# PCB_mezzanine_clock_template.net
KiCad netlist of a schematic drawn in Altium Designer
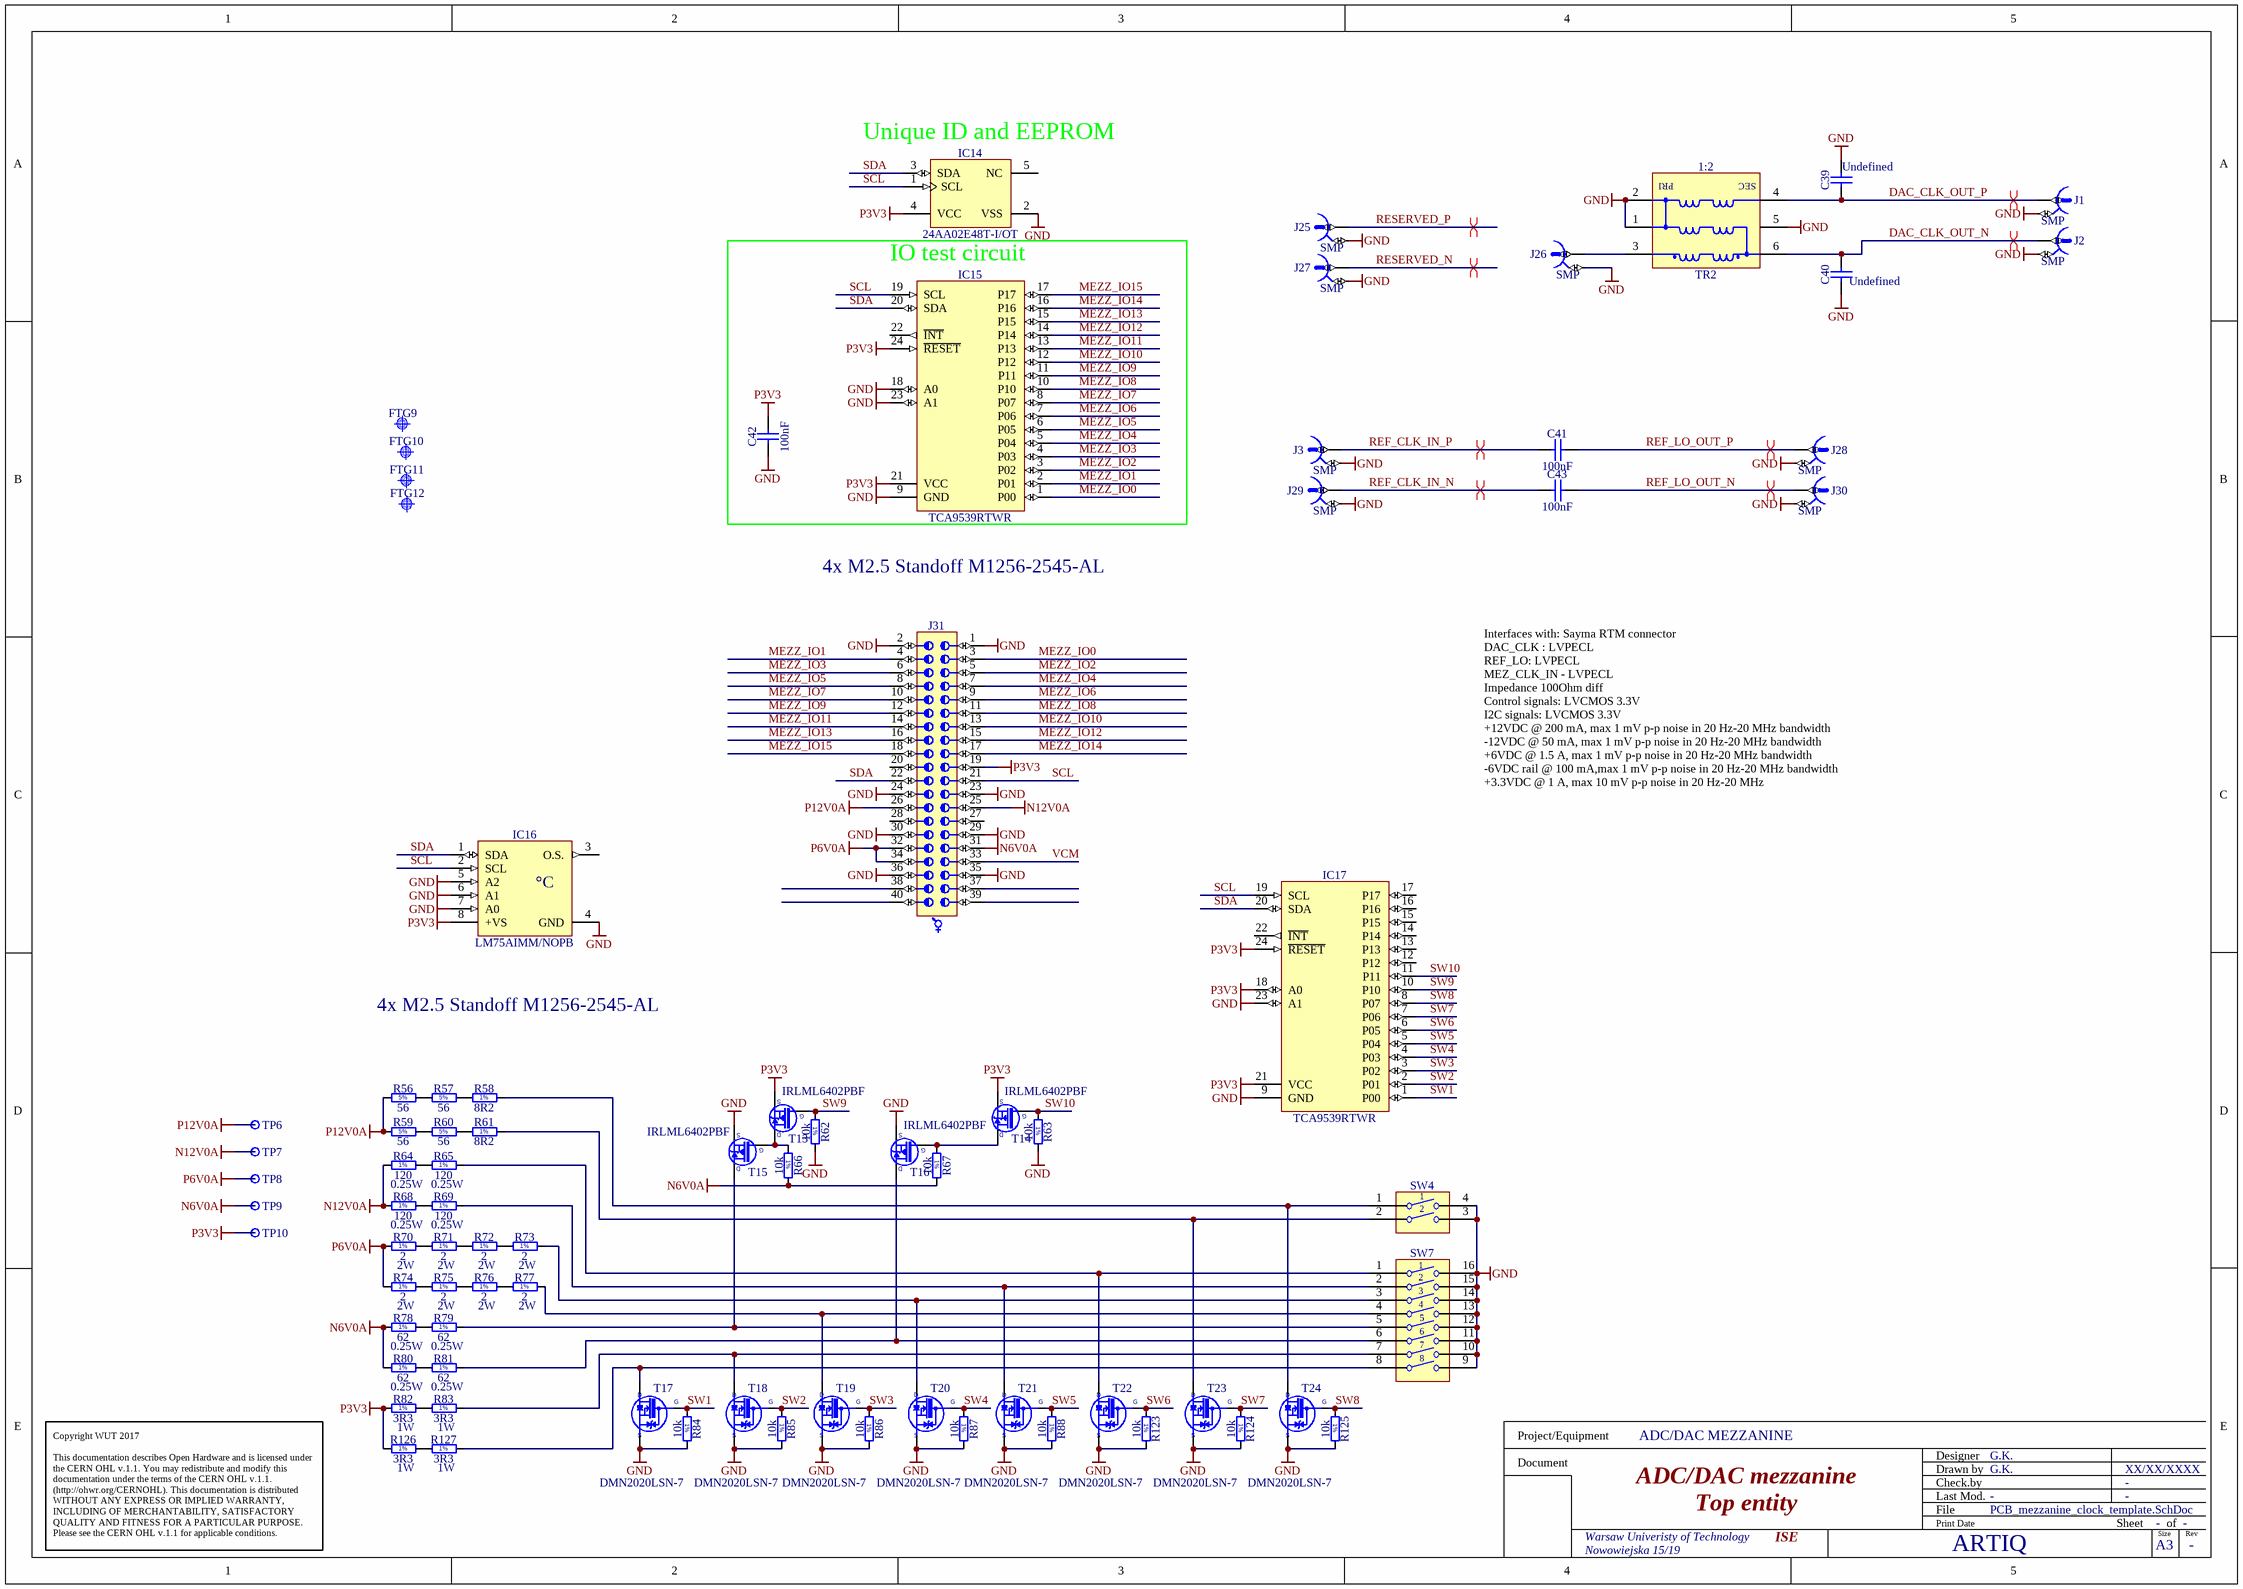
[diagram p0: PCB_mezzanine_clock_template.SchDoc]

(export (version "E")
  (design (tool "Eeschema 10.0.6"))
  (components
    (comp (ref "C39")
      (value "Undefined")
      (footprint "CAPC1005X55N")
      (description "Non-polarised capacitor")
      (fields (field (name "PART NUMBER") "CC0402_NO-VALUE") (field (name "AUTHOR") "CERN DEM JLC"))
      (libsource (lib "Capacitors") (part "Capacitor - non polarized"))
    )
    (comp (ref "C40")
      (value "Undefined")
      (footprint "CAPC1005X55N")
      (description "Non-polarised capacitor")
      (fields (field (name "PART NUMBER") "CC0402_NO-VALUE") (field (name "AUTHOR") "CERN DEM JLC"))
      (libsource (lib "Capacitors") (part "Capacitor - non polarized"))
    )
    (comp (ref "C41")
      (value "100nF")
      (footprint "CAPC1005X55N")
      (description "Non-polarised capacitor")
      (fields
        (field (name "PART NUMBER") "CC0402_100NF_16V_10%_X5R")
        (field (name "VOLTAGE") "16V")
        (field (name "AUTHOR") "CERN DEM JLC")
      )
      (libsource (lib "Capacitors") (part "Capacitor - non polarized"))
    )
    (comp (ref "C42")
      (value "100nF")
      (footprint "CAPC1005X55N")
      (description "Non-polarised capacitor")
      (fields
        (field (name "PART NUMBER") "CC0402_100NF_16V_10%_X5R")
        (field (name "VOLTAGE") "16V")
        (field (name "AUTHOR") "CERN DEM JLC")
      )
      (libsource (lib "Capacitors") (part "Capacitor - non polarized"))
    )
    (comp (ref "C43")
      (value "100nF")
      (footprint "CAPC1005X55N")
      (description "Non-polarised capacitor")
      (fields
        (field (name "PART NUMBER") "CC0402_100NF_16V_10%_X5R")
        (field (name "VOLTAGE") "16V")
        (field (name "AUTHOR") "CERN DEM JLC")
      )
      (libsource (lib "Capacitors") (part "Capacitor - non polarized"))
    )
    (comp (ref "FTG9")
      (value "Use only in PCB")
      (footprint "FIDUCIAL_TOP_C100-200")
      (description "Fiducial Target")
      (fields (field (name "PART NUMBER") "FIDUCIAL_TARGET_C100-200") (field (name "AUTHOR") "CERN DEM JLC"))
      (libsource (lib "Eletro-mechanical") (part "Fiducial Target"))
    )
    (comp (ref "FTG10")
      (value "Use only in PCB")
      (footprint "FIDUCIAL_TOP_S100-200")
      (description "Fiducial Target")
      (fields (field (name "PART NUMBER") "FIDUCIAL_TARGET_S100-200") (field (name "AUTHOR") "CERN DEM JLC"))
      (libsource (lib "Eletro-mechanical") (part "Fiducial Target"))
    )
    (comp (ref "FTG11")
      (value "Use only in PCB")
      (footprint "FIDUCIAL_TOP_S200-400")
      (description "Fiducial Target")
      (fields (field (name "PART NUMBER") "FIDUCIAL_TARGET_S200-400") (field (name "AUTHOR") "CERN DEM JLC"))
      (libsource (lib "Eletro-mechanical") (part "Fiducial Target"))
    )
    (comp (ref "FTG12")
      (value "Use only in PCB")
      (footprint "FIDUCIAL_TOP_S100-200")
      (description "Fiducial Target")
      (fields (field (name "PART NUMBER") "FIDUCIAL_TARGET_S100-200") (field (name "AUTHOR") "CERN DEM JLC"))
      (libsource (lib "Eletro-mechanical") (part "Fiducial Target"))
    )
    (comp (ref "IC14")
      (value "24AA02E48T-I/OT")
      (footprint "SOT95P280X145-5N")
      (description "1.7V-5.5V, 2K I2C Serial EEPROM With EUI-48 Node Identity")
      (fields (field (name "MANUFACTURER") "MICROCHIP TECHNOLOGY") (field (name "AUTHOR") "CERN DEM MR"))
      (libsource (lib "ICs And Semiconductors") (part "24AA02E48T-I/OT"))
    )
    (comp (ref "IC15")
      (value "TCA9539RTWR")
      (footprint "QFN50P400X400X80-25N-S255")
      (description "Low-Voltage 16-Bit I2C and SMBus I/O Expander")
      (fields (field (name "MANUFACTURER") "TEXAS INSTRUMENTS") (field (name "AUTHOR") "CERN DEM MR"))
      (libsource (lib "ICs And Semiconductors") (part "TCA9539RTWR"))
    )
    (comp (ref "IC16")
      (value "LM75AIMM/NOPB")
      (footprint "SOP65P490X109-8N")
      (description "Digital Temperature Sensor and Thermal Watchdog with Two-Wire Interface")
      (fields (field (name "MANUFACTURER") "TEXAS INSTRUMENTS") (field (name "AUTHOR") "CERN DEM JLC"))
      (libsource (lib "ICs And Semiconductors") (part "LM75"))
    )
    (comp (ref "IC17")
      (value "TCA9539RTWR")
      (footprint "QFN50P400X400X80-25N-S255")
      (description "Low-Voltage 16-Bit I2C and SMBus I/O Expander")
      (fields (field (name "MANUFACTURER") "TEXAS INSTRUMENTS") (field (name "AUTHOR") "CERN DEM MR"))
      (libsource (lib "ICs And Semiconductors") (part "TCA9539RTWR"))
    )
    (comp (ref "J1")
      (value "SMP")
      (footprint "MOLEX_85305-0232")
      (fields
        (field (name "PART NUMBER") "MOLEX_85305-0232")
        (field (name "MANUFACTURER") "MOLEX")
        (field (name "MANUFACTURER PART NUMBER") "85305-0232")
        (field (name "AUTHOR") "CERN DEM JMW")
      )
      (libsource (lib "") (part "Coax_1Male_1Shield_1"))
    )
    (comp (ref "J2")
      (value "SMP")
      (footprint "MOLEX_85305-0232")
      (fields
        (field (name "PART NUMBER") "MOLEX_85305-0232")
        (field (name "MANUFACTURER") "MOLEX")
        (field (name "MANUFACTURER PART NUMBER") "85305-0232")
        (field (name "AUTHOR") "CERN DEM JMW")
      )
      (libsource (lib "") (part "Coax_1Male_1Shield_1"))
    )
    (comp (ref "J3")
      (value "SMP")
      (footprint "MOLEX_85305-0232")
      (fields
        (field (name "PART NUMBER") "MOLEX_85305-0232")
        (field (name "MANUFACTURER") "MOLEX")
        (field (name "MANUFACTURER PART NUMBER") "85305-0232")
        (field (name "AUTHOR") "CERN DEM JMW")
      )
      (libsource (lib "Connectors") (part "Coax_1Male_1Shield"))
    )
    (comp (ref "J25")
      (value "SMP")
      (footprint "MOLEX_85305-0232")
      (fields
        (field (name "PART NUMBER") "MOLEX_85305-0232")
        (field (name "MANUFACTURER") "MOLEX")
        (field (name "MANUFACTURER PART NUMBER") "85305-0232")
        (field (name "AUTHOR") "CERN DEM JMW")
      )
      (libsource (lib "Connectors") (part "Coax_1Male_1Shield"))
    )
    (comp (ref "J26")
      (value "SMP")
      (footprint "MOLEX_73415-3591")
      (fields
        (field (name "PART NUMBER") "MOLEX_73415-3591")
        (field (name "MANUFACTURER") "MOLEX")
        (field (name "MANUFACTURER PART NUMBER") "73415-3591")
        (field (name "AUTHOR") "CERN DEM JMW")
      )
      (libsource (lib "Connectors") (part "Coax_1Male_1Shield"))
    )
    (comp (ref "J27")
      (value "SMP")
      (footprint "MOLEX_85305-0232")
      (fields
        (field (name "PART NUMBER") "MOLEX_85305-0232")
        (field (name "MANUFACTURER") "MOLEX")
        (field (name "MANUFACTURER PART NUMBER") "85305-0232")
        (field (name "AUTHOR") "CERN DEM JMW")
      )
      (libsource (lib "Connectors") (part "Coax_1Male_1Shield"))
    )
    (comp (ref "J28")
      (value "SMP")
      (footprint "MOLEX_85305-0232")
      (fields
        (field (name "PART NUMBER") "MOLEX_85305-0232")
        (field (name "MANUFACTURER") "MOLEX")
        (field (name "MANUFACTURER PART NUMBER") "85305-0232")
        (field (name "AUTHOR") "CERN DEM JMW")
      )
      (libsource (lib "") (part "Coax_1Male_1Shield_1"))
    )
    (comp (ref "J29")
      (value "SMP")
      (footprint "MOLEX_85305-0232")
      (fields
        (field (name "PART NUMBER") "MOLEX_85305-0232")
        (field (name "MANUFACTURER") "MOLEX")
        (field (name "MANUFACTURER PART NUMBER") "85305-0232")
        (field (name "AUTHOR") "CERN DEM JMW")
      )
      (libsource (lib "Connectors") (part "Coax_1Male_1Shield"))
    )
    (comp (ref "J30")
      (value "SMP")
      (footprint "MOLEX_85305-0232")
      (fields
        (field (name "PART NUMBER") "MOLEX_85305-0232")
        (field (name "MANUFACTURER") "MOLEX")
        (field (name "MANUFACTURER PART NUMBER") "85305-0232")
        (field (name "AUTHOR") "CERN DEM JMW")
      )
      (libsource (lib "") (part "Coax_1Male_1Shield_1"))
    )
    (comp (ref "J31")
      (value "~")
      (footprint "SAMTEC_LSS-120-02-L-DV-A")
      (fields
        (field (name "PART NUMBER") "SAMTEC_LSS-120-02-L-DV-A")
        (field (name "MANUFACTURER") "SAMTEC")
        (field (name "MANUFACTURER PART NUMBER") "LSS-120-02-L-DV-A")
        (field (name "AUTHOR") "CERN DEM JMW")
      )
      (libsource (lib "LIBRARY_SCH") (part "CON_SAMTEC_LSS-120-02-L-DV-A"))
    )
    (comp (ref "R56")
      (value "56")
      (footprint "RESC6331X70N")
      (description "Resistor - 5%")
      (fields
        (field (name "PART NUMBER") "R2512_56R_5%_1W_200PPM")
        (field (name "POWER") "1W")
        (field (name "AUTHOR") "CERN DEM JLC")
      )
      (libsource (lib "Resistors") (part "Resistor - 5%"))
    )
    (comp (ref "R57")
      (value "56")
      (footprint "RESC6331X70N")
      (description "Resistor - 5%")
      (fields
        (field (name "PART NUMBER") "R2512_56R_5%_1W_200PPM")
        (field (name "POWER") "1W")
        (field (name "AUTHOR") "CERN DEM JLC")
      )
      (libsource (lib "Resistors") (part "Resistor - 5%"))
    )
    (comp (ref "R58")
      (value "8R2")
      (footprint "RESC3216X65N")
      (description "Resistor - 1%")
      (fields
        (field (name "PART NUMBER") "R1206_8R2_1%_0.25W_200PPM")
        (field (name "POWER") "0.25W")
        (field (name "AUTHOR") "CERN DEM JLC")
      )
      (libsource (lib "Resistors") (part "Resistor - 1%"))
    )
    (comp (ref "R59")
      (value "56")
      (footprint "RESC6331X70N")
      (description "Resistor - 5%")
      (fields
        (field (name "PART NUMBER") "R2512_56R_5%_1W_200PPM")
        (field (name "POWER") "1W")
        (field (name "AUTHOR") "CERN DEM JLC")
      )
      (libsource (lib "Resistors") (part "Resistor - 5%"))
    )
    (comp (ref "R60")
      (value "56")
      (footprint "RESC6331X70N")
      (description "Resistor - 5%")
      (fields
        (field (name "PART NUMBER") "R2512_56R_5%_1W_200PPM")
        (field (name "POWER") "1W")
        (field (name "AUTHOR") "CERN DEM JLC")
      )
      (libsource (lib "Resistors") (part "Resistor - 5%"))
    )
    (comp (ref "R61")
      (value "8R2")
      (footprint "RESC3216X65N")
      (description "Resistor - 1%")
      (fields
        (field (name "PART NUMBER") "R1206_8R2_1%_0.25W_200PPM")
        (field (name "POWER") "0.25W")
        (field (name "AUTHOR") "CERN DEM JLC")
      )
      (libsource (lib "Resistors") (part "Resistor - 1%"))
    )
    (comp (ref "R62")
      (value "10k")
      (footprint "RESC1005X40N")
      (description "Resistor - 1%")
      (fields
        (field (name "PART NUMBER") "R0402_10K_1%_0.0625W_100PPM")
        (field (name "POWER") "0.0625W")
        (field (name "AUTHOR") "CERN DEM JLC")
      )
      (libsource (lib "Resistors") (part "Resistor - 1%"))
    )
    (comp (ref "R63")
      (value "10k")
      (footprint "RESC1005X40N")
      (description "Resistor - 1%")
      (fields
        (field (name "PART NUMBER") "R0402_10K_1%_0.0625W_100PPM")
        (field (name "POWER") "0.0625W")
        (field (name "AUTHOR") "CERN DEM JLC")
      )
      (libsource (lib "Resistors") (part "Resistor - 1%"))
    )
    (comp (ref "R64")
      (value "120")
      (footprint "RESC3216X65N")
      (description "Resistor - 1%")
      (fields
        (field (name "PART NUMBER") "R1206_120R_1%_0.25W_100PPM")
        (field (name "POWER") "0.25W")
        (field (name "TOLERANCE") "±1%")
        (field (name "AUTHOR") "CERN DEM JLC")
      )
      (libsource (lib "Resistors") (part "Resistor - 1%"))
    )
    (comp (ref "R65")
      (value "120")
      (footprint "RESC3216X65N")
      (description "Resistor - 1%")
      (fields
        (field (name "PART NUMBER") "R1206_120R_1%_0.25W_100PPM")
        (field (name "POWER") "0.25W")
        (field (name "TOLERANCE") "±1%")
        (field (name "AUTHOR") "CERN DEM JLC")
      )
      (libsource (lib "Resistors") (part "Resistor - 1%"))
    )
    (comp (ref "R66")
      (value "10k")
      (footprint "RESC1005X40N")
      (description "Resistor - 1%")
      (fields
        (field (name "PART NUMBER") "R0402_10K_1%_0.0625W_100PPM")
        (field (name "POWER") "0.0625W")
        (field (name "AUTHOR") "CERN DEM JLC")
      )
      (libsource (lib "Resistors") (part "Resistor - 1%"))
    )
    (comp (ref "R67")
      (value "10k")
      (footprint "RESC1005X40N")
      (description "Resistor - 1%")
      (fields
        (field (name "PART NUMBER") "R0402_10K_1%_0.0625W_100PPM")
        (field (name "POWER") "0.0625W")
        (field (name "AUTHOR") "CERN DEM JLC")
      )
      (libsource (lib "Resistors") (part "Resistor - 1%"))
    )
    (comp (ref "R68")
      (value "120")
      (footprint "RESC3216X65N")
      (description "Resistor - 1%")
      (fields
        (field (name "PART NUMBER") "R1206_120R_1%_0.25W_100PPM")
        (field (name "POWER") "0.25W")
        (field (name "TOLERANCE") "±1%")
        (field (name "AUTHOR") "CERN DEM JLC")
      )
      (libsource (lib "Resistors") (part "Resistor - 1%"))
    )
    (comp (ref "R69")
      (value "120")
      (footprint "RESC3216X65N")
      (description "Resistor - 1%")
      (fields
        (field (name "PART NUMBER") "R1206_120R_1%_0.25W_100PPM")
        (field (name "POWER") "0.25W")
        (field (name "TOLERANCE") "±1%")
        (field (name "AUTHOR") "CERN DEM JLC")
      )
      (libsource (lib "Resistors") (part "Resistor - 1%"))
    )
    (comp (ref "R70")
      (value "2")
      (footprint "RESM11670X449N")
      (description "Resistor - 1%")
      (fields
        (field (name "PART NUMBER") "R4527_2R_1%_2W_50PPM")
        (field (name "POWER") "2W")
        (field (name "TOLERANCE") "±1%")
        (field (name "AUTHOR") "CERN DEM JLC")
      )
      (libsource (lib "Resistors") (part "Resistor - 1%"))
    )
    (comp (ref "R71")
      (value "2")
      (footprint "RESM11670X449N")
      (description "Resistor - 1%")
      (fields
        (field (name "PART NUMBER") "R4527_2R_1%_2W_50PPM")
        (field (name "POWER") "2W")
        (field (name "TOLERANCE") "±1%")
        (field (name "AUTHOR") "CERN DEM JLC")
      )
      (libsource (lib "Resistors") (part "Resistor - 1%"))
    )
    (comp (ref "R72")
      (value "2")
      (footprint "RESM11670X449N")
      (description "Resistor - 1%")
      (fields
        (field (name "PART NUMBER") "R4527_2R_1%_2W_50PPM")
        (field (name "POWER") "2W")
        (field (name "TOLERANCE") "±1%")
        (field (name "AUTHOR") "CERN DEM JLC")
      )
      (libsource (lib "Resistors") (part "Resistor - 1%"))
    )
    (comp (ref "R73")
      (value "2")
      (footprint "RESM11670X449N")
      (description "Resistor - 1%")
      (fields
        (field (name "PART NUMBER") "R4527_2R_1%_2W_50PPM")
        (field (name "POWER") "2W")
        (field (name "TOLERANCE") "±1%")
        (field (name "AUTHOR") "CERN DEM JLC")
      )
      (libsource (lib "Resistors") (part "Resistor - 1%"))
    )
    (comp (ref "R74")
      (value "2")
      (footprint "RESM11670X449N")
      (description "Resistor - 1%")
      (fields
        (field (name "PART NUMBER") "R4527_2R_1%_2W_50PPM")
        (field (name "POWER") "2W")
        (field (name "TOLERANCE") "±1%")
        (field (name "AUTHOR") "CERN DEM JLC")
      )
      (libsource (lib "Resistors") (part "Resistor - 1%"))
    )
    (comp (ref "R75")
      (value "2")
      (footprint "RESM11670X449N")
      (description "Resistor - 1%")
      (fields
        (field (name "PART NUMBER") "R4527_2R_1%_2W_50PPM")
        (field (name "POWER") "2W")
        (field (name "TOLERANCE") "±1%")
        (field (name "AUTHOR") "CERN DEM JLC")
      )
      (libsource (lib "Resistors") (part "Resistor - 1%"))
    )
    (comp (ref "R76")
      (value "2")
      (footprint "RESM11670X449N")
      (description "Resistor - 1%")
      (fields
        (field (name "PART NUMBER") "R4527_2R_1%_2W_50PPM")
        (field (name "POWER") "2W")
        (field (name "TOLERANCE") "±1%")
        (field (name "AUTHOR") "CERN DEM JLC")
      )
      (libsource (lib "Resistors") (part "Resistor - 1%"))
    )
    (comp (ref "R77")
      (value "2")
      (footprint "RESM11670X449N")
      (description "Resistor - 1%")
      (fields
        (field (name "PART NUMBER") "R4527_2R_1%_2W_50PPM")
        (field (name "POWER") "2W")
        (field (name "TOLERANCE") "±1%")
        (field (name "AUTHOR") "CERN DEM JLC")
      )
      (libsource (lib "Resistors") (part "Resistor - 1%"))
    )
    (comp (ref "R78")
      (value "62")
      (footprint "RESC3216X65N")
      (description "Resistor - 1%")
      (fields
        (field (name "PART NUMBER") "R1206_62R_1%_0.25W_100PPM")
        (field (name "POWER") "0.25W")
        (field (name "TOLERANCE") "±1%")
        (field (name "AUTHOR") "CERN DEM JLC")
      )
      (libsource (lib "Resistors") (part "Resistor - 1%"))
    )
    (comp (ref "R79")
      (value "62")
      (footprint "RESC3216X65N")
      (description "Resistor - 1%")
      (fields
        (field (name "PART NUMBER") "R1206_62R_1%_0.25W_100PPM")
        (field (name "POWER") "0.25W")
        (field (name "TOLERANCE") "±1%")
        (field (name "AUTHOR") "CERN DEM JLC")
      )
      (libsource (lib "Resistors") (part "Resistor - 1%"))
    )
    (comp (ref "R80")
      (value "62")
      (footprint "RESC3216X65N")
      (description "Resistor - 1%")
      (fields
        (field (name "PART NUMBER") "R1206_62R_1%_0.25W_100PPM")
        (field (name "POWER") "0.25W")
        (field (name "TOLERANCE") "±1%")
        (field (name "AUTHOR") "CERN DEM JLC")
      )
      (libsource (lib "Resistors") (part "Resistor - 1%"))
    )
    (comp (ref "R81")
      (value "62")
      (footprint "RESC3216X65N")
      (description "Resistor - 1%")
      (fields
        (field (name "PART NUMBER") "R1206_62R_1%_0.25W_100PPM")
        (field (name "POWER") "0.25W")
        (field (name "TOLERANCE") "±1%")
        (field (name "AUTHOR") "CERN DEM JLC")
      )
      (libsource (lib "Resistors") (part "Resistor - 1%"))
    )
    (comp (ref "R82")
      (value "3R3")
      (footprint "RESC6331X70N")
      (description "Resistor - 1%")
      (fields
        (field (name "PART NUMBER") "R2512_3R3_1%_1W_200PPM")
        (field (name "POWER") "1W")
        (field (name "TOLERANCE") "±1%")
        (field (name "AUTHOR") "CERN DEM JLC")
      )
      (libsource (lib "Resistors") (part "Resistor - 1%"))
    )
    (comp (ref "R83")
      (value "3R3")
      (footprint "RESC6331X70N")
      (description "Resistor - 1%")
      (fields
        (field (name "PART NUMBER") "R2512_3R3_1%_1W_200PPM")
        (field (name "POWER") "1W")
        (field (name "TOLERANCE") "±1%")
        (field (name "AUTHOR") "CERN DEM JLC")
      )
      (libsource (lib "Resistors") (part "Resistor - 1%"))
    )
    (comp (ref "R84")
      (value "10k")
      (footprint "RESC1005X40N")
      (description "Resistor - 1%")
      (fields
        (field (name "PART NUMBER") "R0402_10K_1%_0.0625W_100PPM")
        (field (name "POWER") "0.0625W")
        (field (name "AUTHOR") "CERN DEM JLC")
      )
      (libsource (lib "Resistors") (part "Resistor - 1%"))
    )
    (comp (ref "R85")
      (value "10k")
      (footprint "RESC1005X40N")
      (description "Resistor - 1%")
      (fields
        (field (name "PART NUMBER") "R0402_10K_1%_0.0625W_100PPM")
        (field (name "POWER") "0.0625W")
        (field (name "AUTHOR") "CERN DEM JLC")
      )
      (libsource (lib "Resistors") (part "Resistor - 1%"))
    )
    (comp (ref "R86")
      (value "10k")
      (footprint "RESC1005X40N")
      (description "Resistor - 1%")
      (fields
        (field (name "PART NUMBER") "R0402_10K_1%_0.0625W_100PPM")
        (field (name "POWER") "0.0625W")
        (field (name "AUTHOR") "CERN DEM JLC")
      )
      (libsource (lib "Resistors") (part "Resistor - 1%"))
    )
    (comp (ref "R87")
      (value "10k")
      (footprint "RESC1005X40N")
      (description "Resistor - 1%")
      (fields
        (field (name "PART NUMBER") "R0402_10K_1%_0.0625W_100PPM")
        (field (name "POWER") "0.0625W")
        (field (name "AUTHOR") "CERN DEM JLC")
      )
      (libsource (lib "Resistors") (part "Resistor - 1%"))
    )
    (comp (ref "R88")
      (value "10k")
      (footprint "RESC1005X40N")
      (description "Resistor - 1%")
      (fields
        (field (name "PART NUMBER") "R0402_10K_1%_0.0625W_100PPM")
        (field (name "POWER") "0.0625W")
        (field (name "AUTHOR") "CERN DEM JLC")
      )
      (libsource (lib "Resistors") (part "Resistor - 1%"))
    )
    (comp (ref "R123")
      (value "10k")
      (footprint "RESC1005X40N")
      (description "Resistor - 1%")
      (fields
        (field (name "PART NUMBER") "R0402_10K_1%_0.0625W_100PPM")
        (field (name "POWER") "0.0625W")
        (field (name "AUTHOR") "CERN DEM JLC")
      )
      (libsource (lib "Resistors") (part "Resistor - 1%"))
    )
    (comp (ref "R124")
      (value "10k")
      (footprint "RESC1005X40N")
      (description "Resistor - 1%")
      (fields
        (field (name "PART NUMBER") "R0402_10K_1%_0.0625W_100PPM")
        (field (name "POWER") "0.0625W")
        (field (name "AUTHOR") "CERN DEM JLC")
      )
      (libsource (lib "Resistors") (part "Resistor - 1%"))
    )
    (comp (ref "R125")
      (value "10k")
      (footprint "RESC1005X40N")
      (description "Resistor - 1%")
      (fields
        (field (name "PART NUMBER") "R0402_10K_1%_0.0625W_100PPM")
        (field (name "POWER") "0.0625W")
        (field (name "AUTHOR") "CERN DEM JLC")
      )
      (libsource (lib "Resistors") (part "Resistor - 1%"))
    )
    (comp (ref "R126")
      (value "3R3")
      (footprint "RESC6331X70N")
      (description "Resistor - 1%")
      (fields
        (field (name "PART NUMBER") "R2512_3R3_1%_1W_200PPM")
        (field (name "POWER") "1W")
        (field (name "TOLERANCE") "±1%")
        (field (name "AUTHOR") "CERN DEM JLC")
      )
      (libsource (lib "Resistors") (part "Resistor - 1%"))
    )
    (comp (ref "R127")
      (value "3R3")
      (footprint "RESC6331X70N")
      (description "Resistor - 1%")
      (fields
        (field (name "PART NUMBER") "R2512_3R3_1%_1W_200PPM")
        (field (name "POWER") "1W")
        (field (name "TOLERANCE") "±1%")
        (field (name "AUTHOR") "CERN DEM JLC")
      )
      (libsource (lib "Resistors") (part "Resistor - 1%"))
    )
    (comp (ref "SW4")
      (value "Switch")
      (footprint "SW_OMRON_A6S-2102-H")
      (description "2 Ways SPST DIP Switch")
      (fields
        (field (name "PART NUMBER") "SW_OMRON_A6S-2102-H")
        (field (name "MANUFACTURER") "OMRON")
        (field (name "AUTHOR") "CERN DEM JMW")
      )
      (libsource (lib "Eletro-mechanical") (part "SW 2x SPST DIP Switch"))
    )
    (comp (ref "SW7")
      (value "Switch")
      (footprint "SW_OMRON_A6S-8102-H")
      (description "8 Ways SPST DIP Switch")
      (fields
        (field (name "PART NUMBER") "SW_OMRON_A6S-8102-H")
        (field (name "MANUFACTURER") "OMRON")
        (field (name "AUTHOR") "CERN DEM JMW")
      )
      (libsource (lib "Eletro-mechanical") (part "SW 8x SPST DIP Switch"))
    )
    (comp (ref "T13")
      (value "IRLML6402PBF")
      (footprint "SOT95P237X112-3N")
      (description "P-CHANNEL MOSFET WITH ZENER DIODE")
      (fields (field (name "MANUFACTURER") "INTERNATIONAL RECTIFIER") (field (name "AUTHOR") "CERN DEM JLC"))
      (libsource (lib "ICs And Semiconductors") (part "P-MOSFET-DZ 1G 2S 3D"))
    )
    (comp (ref "T14")
      (value "IRLML6402PBF")
      (footprint "SOT95P237X112-3N")
      (description "P-CHANNEL MOSFET WITH ZENER DIODE")
      (fields (field (name "MANUFACTURER") "INTERNATIONAL RECTIFIER") (field (name "AUTHOR") "CERN DEM JLC"))
      (libsource (lib "ICs And Semiconductors") (part "P-MOSFET-DZ 1G 2S 3D"))
    )
    (comp (ref "T15")
      (value "IRLML6402PBF")
      (footprint "SOT95P237X112-3N")
      (description "P-CHANNEL MOSFET WITH ZENER DIODE")
      (fields (field (name "MANUFACTURER") "INTERNATIONAL RECTIFIER") (field (name "AUTHOR") "CERN DEM JLC"))
      (libsource (lib "ICs And Semiconductors") (part "P-MOSFET-DZ 1G 2S 3D"))
    )
    (comp (ref "T16")
      (value "IRLML6402PBF")
      (footprint "SOT95P237X112-3N")
      (description "P-CHANNEL MOSFET WITH ZENER DIODE")
      (fields (field (name "MANUFACTURER") "INTERNATIONAL RECTIFIER") (field (name "AUTHOR") "CERN DEM JLC"))
      (libsource (lib "ICs And Semiconductors") (part "P-MOSFET-DZ 1G 2S 3D"))
    )
    (comp (ref "T17")
      (value "DMN2020LSN-7")
      (footprint "SOT95P285X140-3N")
      (description "20V, 6.9A, N-Channel Enhancement Mode MOSFET")
      (fields (field (name "MANUFACTURER") "DIODES INCORPORATED") (field (name "AUTHOR") "CERN DEM JLC"))
      (libsource (lib "ICs And Semiconductors") (part "DMN2020LSN-7"))
    )
    (comp (ref "T18")
      (value "DMN2020LSN-7")
      (footprint "SOT95P285X140-3N")
      (description "20V, 6.9A, N-Channel Enhancement Mode MOSFET")
      (fields (field (name "MANUFACTURER") "DIODES INCORPORATED") (field (name "AUTHOR") "CERN DEM JLC"))
      (libsource (lib "ICs And Semiconductors") (part "DMN2020LSN-7"))
    )
    (comp (ref "T19")
      (value "DMN2020LSN-7")
      (footprint "SOT95P285X140-3N")
      (description "20V, 6.9A, N-Channel Enhancement Mode MOSFET")
      (fields (field (name "MANUFACTURER") "DIODES INCORPORATED") (field (name "AUTHOR") "CERN DEM JLC"))
      (libsource (lib "ICs And Semiconductors") (part "DMN2020LSN-7"))
    )
    (comp (ref "T20")
      (value "DMN2020LSN-7")
      (footprint "SOT95P285X140-3N")
      (description "20V, 6.9A, N-Channel Enhancement Mode MOSFET")
      (fields (field (name "MANUFACTURER") "DIODES INCORPORATED") (field (name "AUTHOR") "CERN DEM JLC"))
      (libsource (lib "ICs And Semiconductors") (part "DMN2020LSN-7"))
    )
    (comp (ref "T21")
      (value "DMN2020LSN-7")
      (footprint "SOT95P285X140-3N")
      (description "20V, 6.9A, N-Channel Enhancement Mode MOSFET")
      (fields (field (name "MANUFACTURER") "DIODES INCORPORATED") (field (name "AUTHOR") "CERN DEM JLC"))
      (libsource (lib "ICs And Semiconductors") (part "DMN2020LSN-7"))
    )
    (comp (ref "T22")
      (value "DMN2020LSN-7")
      (footprint "SOT95P285X140-3N")
      (description "20V, 6.9A, N-Channel Enhancement Mode MOSFET")
      (fields (field (name "MANUFACTURER") "DIODES INCORPORATED") (field (name "AUTHOR") "CERN DEM JLC"))
      (libsource (lib "ICs And Semiconductors") (part "DMN2020LSN-7"))
    )
    (comp (ref "T23")
      (value "DMN2020LSN-7")
      (footprint "SOT95P285X140-3N")
      (description "20V, 6.9A, N-Channel Enhancement Mode MOSFET")
      (fields (field (name "MANUFACTURER") "DIODES INCORPORATED") (field (name "AUTHOR") "CERN DEM JLC"))
      (libsource (lib "ICs And Semiconductors") (part "DMN2020LSN-7"))
    )
    (comp (ref "T24")
      (value "DMN2020LSN-7")
      (footprint "SOT95P285X140-3N")
      (description "20V, 6.9A, N-Channel Enhancement Mode MOSFET")
      (fields (field (name "MANUFACTURER") "DIODES INCORPORATED") (field (name "AUTHOR") "CERN DEM JLC"))
      (libsource (lib "ICs And Semiconductors") (part "DMN2020LSN-7"))
    )
    (comp (ref "TP6")
      (value "Test Point")
      (footprint "TPS127")
      (fields (field (name "PART NUMBER") "SMD_PAD_1.27X1.27MM") (field (name "AUTHOR") "CERN DEM JLC"))
      (libsource (lib "Eletro-mechanical") (part "Test Point"))
    )
    (comp (ref "TP7")
      (value "Test Point")
      (footprint "TPS127")
      (fields (field (name "PART NUMBER") "SMD_PAD_1.27X1.27MM") (field (name "AUTHOR") "CERN DEM JLC"))
      (libsource (lib "Eletro-mechanical") (part "Test Point"))
    )
    (comp (ref "TP8")
      (value "Test Point")
      (footprint "TPS127")
      (fields (field (name "PART NUMBER") "SMD_PAD_1.27X1.27MM") (field (name "AUTHOR") "CERN DEM JLC"))
      (libsource (lib "Eletro-mechanical") (part "Test Point"))
    )
    (comp (ref "TP9")
      (value "Test Point")
      (footprint "TPS127")
      (fields (field (name "PART NUMBER") "SMD_PAD_1.27X1.27MM") (field (name "AUTHOR") "CERN DEM JLC"))
      (libsource (lib "Eletro-mechanical") (part "Test Point"))
    )
    (comp (ref "TP10")
      (value "Test Point")
      (footprint "TPS127")
      (fields (field (name "PART NUMBER") "SMD_PAD_1.27X1.27MM") (field (name "AUTHOR") "CERN DEM JLC"))
      (libsource (lib "Eletro-mechanical") (part "Test Point"))
    )
    (comp (ref "TR2")
      (value "1:2")
      (footprint "XFMR_MINI-CIRCUITS_DB1627")
      (description "50 OHMS 10 to 4000 MHz RF Transformer")
      (fields
        (field (name "PART NUMBER") "XFMR_MINI-CIRCUITS_TCM2-43X+")
        (field (name "POWER") "0.4W")
        (field (name "AUTHOR") "CERN DEM BC")
      )
      (libsource (lib "Inductors & Transformers") (part "XFMR_MINI-CIRCUITS_TCM2-43X"))
    )
  )
  (nets
    (net (code "1") (name "/DAC_CLK_OUT_N") (class "Default")
      (node (ref "C40") (pin "2") (pinfunction "2_2") (pintype "passive"))
      (node (ref "J2") (pin "1") (pinfunction "1_1") (pintype "bidirectional"))
      (node (ref "TR2") (pin "6") (pinfunction "S1_6") (pintype "passive"))
    )
    (net (code "2") (name "/DAC_CLK_OUT_P") (class "Default")
      (node (ref "C39") (pin "1") (pinfunction "1_1") (pintype "passive"))
      (node (ref "J1") (pin "1") (pinfunction "1_1") (pintype "bidirectional"))
      (node (ref "TR2") (pin "4") (pinfunction "S1_4") (pintype "passive"))
    )
    (net (code "3") (name "/MEZZ_IO0") (class "Default")
      (node (ref "IC15") (pin "1") (pinfunction "P00_1") (pintype "bidirectional"))
      (node (ref "J31") (pin "3") (pinfunction "3_3") (pintype "bidirectional"))
    )
    (net (code "4") (name "/MEZZ_IO1") (class "Default")
      (node (ref "IC15") (pin "2") (pinfunction "P01_2") (pintype "bidirectional"))
      (node (ref "J31") (pin "4") (pinfunction "4_4") (pintype "bidirectional"))
    )
    (net (code "5") (name "/MEZZ_IO2") (class "Default")
      (node (ref "IC15") (pin "3") (pinfunction "P02_3") (pintype "bidirectional"))
      (node (ref "J31") (pin "5") (pinfunction "5_5") (pintype "bidirectional"))
    )
    (net (code "6") (name "/MEZZ_IO3") (class "Default")
      (node (ref "IC15") (pin "4") (pinfunction "P03_4") (pintype "bidirectional"))
      (node (ref "J31") (pin "6") (pinfunction "6_6") (pintype "bidirectional"))
    )
    (net (code "7") (name "/MEZZ_IO4") (class "Default")
      (node (ref "IC15") (pin "5") (pinfunction "P04_5") (pintype "bidirectional"))
      (node (ref "J31") (pin "7") (pinfunction "7_7") (pintype "bidirectional"))
    )
    (net (code "8") (name "/MEZZ_IO5") (class "Default")
      (node (ref "IC15") (pin "6") (pinfunction "P05_6") (pintype "bidirectional"))
      (node (ref "J31") (pin "8") (pinfunction "8_8") (pintype "bidirectional"))
    )
    (net (code "9") (name "/MEZZ_IO6") (class "Default")
      (node (ref "IC15") (pin "7") (pinfunction "P06_7") (pintype "bidirectional"))
      (node (ref "J31") (pin "9") (pinfunction "9_9") (pintype "bidirectional"))
    )
    (net (code "10") (name "/MEZZ_IO7") (class "Default")
      (node (ref "IC15") (pin "8") (pinfunction "P07_8") (pintype "bidirectional"))
      (node (ref "J31") (pin "10") (pinfunction "10_10") (pintype "bidirectional"))
    )
    (net (code "11") (name "/MEZZ_IO8") (class "Default")
      (node (ref "IC15") (pin "10") (pinfunction "P10_10") (pintype "bidirectional"))
      (node (ref "J31") (pin "11") (pinfunction "11_11") (pintype "bidirectional"))
    )
    (net (code "12") (name "/MEZZ_IO9") (class "Default")
      (node (ref "IC15") (pin "11") (pinfunction "P11_11") (pintype "bidirectional"))
      (node (ref "J31") (pin "12") (pinfunction "12_12") (pintype "bidirectional"))
    )
    (net (code "13") (name "/MEZZ_IO10") (class "Default")
      (node (ref "IC15") (pin "12") (pinfunction "P12_12") (pintype "bidirectional"))
      (node (ref "J31") (pin "13") (pinfunction "13_13") (pintype "bidirectional"))
    )
    (net (code "14") (name "/MEZZ_IO11") (class "Default")
      (node (ref "IC15") (pin "13") (pinfunction "P13_13") (pintype "bidirectional"))
      (node (ref "J31") (pin "14") (pinfunction "14_14") (pintype "bidirectional"))
    )
    (net (code "15") (name "/MEZZ_IO12") (class "Default")
      (node (ref "IC15") (pin "14") (pinfunction "P14_14") (pintype "bidirectional"))
      (node (ref "J31") (pin "15") (pinfunction "15_15") (pintype "bidirectional"))
    )
    (net (code "16") (name "/MEZZ_IO13") (class "Default")
      (node (ref "IC15") (pin "15") (pinfunction "P15_15") (pintype "bidirectional"))
      (node (ref "J31") (pin "16") (pinfunction "16_16") (pintype "bidirectional"))
    )
    (net (code "17") (name "/MEZZ_IO14") (class "Default")
      (node (ref "IC15") (pin "16") (pinfunction "P16_16") (pintype "bidirectional"))
      (node (ref "J31") (pin "17") (pinfunction "17_17") (pintype "bidirectional"))
    )
    (net (code "18") (name "/MEZZ_IO15") (class "Default")
      (node (ref "IC15") (pin "17") (pinfunction "P17_17") (pintype "bidirectional"))
      (node (ref "J31") (pin "18") (pinfunction "18_18") (pintype "bidirectional"))
    )
    (net (code "19") (name "/REF_CLK_IN_N") (class "Default")
      (node (ref "C43") (pin "1") (pinfunction "1_1") (pintype "passive"))
      (node (ref "J29") (pin "1") (pinfunction "1_1") (pintype "bidirectional"))
    )
    (net (code "20") (name "/REF_CLK_IN_P") (class "Default")
      (node (ref "C41") (pin "1") (pinfunction "1_1") (pintype "passive"))
      (node (ref "J3") (pin "1") (pinfunction "1_1") (pintype "bidirectional"))
    )
    (net (code "21") (name "/REF_LO_OUT_N") (class "Default")
      (node (ref "C43") (pin "2") (pinfunction "2_2") (pintype "passive"))
      (node (ref "J30") (pin "1") (pinfunction "1_1") (pintype "bidirectional"))
    )
    (net (code "22") (name "/REF_LO_OUT_P") (class "Default")
      (node (ref "C41") (pin "2") (pinfunction "2_2") (pintype "passive"))
      (node (ref "J28") (pin "1") (pinfunction "1_1") (pintype "bidirectional"))
    )
    (net (code "23") (name "/RESERVED_N") (class "Default")
      (node (ref "J27") (pin "1") (pinfunction "1_1") (pintype "bidirectional"))
    )
    (net (code "24") (name "/RESERVED_P") (class "Default")
      (node (ref "J25") (pin "1") (pinfunction "1_1") (pintype "bidirectional"))
    )
    (net (code "25") (name "/SCL") (class "Default")
      (node (ref "IC14") (pin "1") (pinfunction "SCL_1") (pintype "input"))
      (node (ref "IC15") (pin "19") (pinfunction "SCL_19") (pintype "input"))
      (node (ref "IC16") (pin "2") (pinfunction "SCL_2") (pintype "input"))
      (node (ref "IC17") (pin "19") (pinfunction "SCL_19") (pintype "input"))
      (node (ref "J31") (pin "21") (pinfunction "21_21") (pintype "bidirectional"))
    )
    (net (code "26") (name "/SDA") (class "Default")
      (node (ref "IC14") (pin "3") (pinfunction "SDA_3") (pintype "bidirectional"))
      (node (ref "IC15") (pin "20") (pinfunction "SDA_20") (pintype "bidirectional"))
      (node (ref "IC16") (pin "1") (pinfunction "SDA_1") (pintype "bidirectional"))
      (node (ref "IC17") (pin "20") (pinfunction "SDA_20") (pintype "bidirectional"))
      (node (ref "J31") (pin "22") (pinfunction "22_22") (pintype "bidirectional"))
    )
    (net (code "27") (name "/SW1") (class "Default")
      (node (ref "IC17") (pin "1") (pinfunction "P00_1") (pintype "bidirectional"))
      (node (ref "R84") (pin "1") (pinfunction "1_1") (pintype "passive"))
      (node (ref "T17") (pin "1") (pinfunction "G_1") (pintype "passive"))
    )
    (net (code "28") (name "/SW2") (class "Default")
      (node (ref "IC17") (pin "2") (pinfunction "P01_2") (pintype "bidirectional"))
      (node (ref "R85") (pin "1") (pinfunction "1_1") (pintype "passive"))
      (node (ref "T18") (pin "1") (pinfunction "G_1") (pintype "passive"))
    )
    (net (code "29") (name "/SW3") (class "Default")
      (node (ref "IC17") (pin "3") (pinfunction "P02_3") (pintype "bidirectional"))
      (node (ref "R86") (pin "1") (pinfunction "1_1") (pintype "passive"))
      (node (ref "T19") (pin "1") (pinfunction "G_1") (pintype "passive"))
    )
    (net (code "30") (name "/SW4") (class "Default")
      (node (ref "IC17") (pin "4") (pinfunction "P03_4") (pintype "bidirectional"))
      (node (ref "R87") (pin "1") (pinfunction "1_1") (pintype "passive"))
      (node (ref "T20") (pin "1") (pinfunction "G_1") (pintype "passive"))
    )
    (net (code "31") (name "/SW5") (class "Default")
      (node (ref "IC17") (pin "5") (pinfunction "P04_5") (pintype "bidirectional"))
      (node (ref "R88") (pin "1") (pinfunction "1_1") (pintype "passive"))
      (node (ref "T21") (pin "1") (pinfunction "G_1") (pintype "passive"))
    )
    (net (code "32") (name "/SW6") (class "Default")
      (node (ref "IC17") (pin "6") (pinfunction "P05_6") (pintype "bidirectional"))
      (node (ref "R123") (pin "1") (pinfunction "1_1") (pintype "passive"))
      (node (ref "T22") (pin "1") (pinfunction "G_1") (pintype "passive"))
    )
    (net (code "33") (name "/SW7") (class "Default")
      (node (ref "IC17") (pin "7") (pinfunction "P06_7") (pintype "bidirectional"))
      (node (ref "R124") (pin "1") (pinfunction "1_1") (pintype "passive"))
      (node (ref "T23") (pin "1") (pinfunction "G_1") (pintype "passive"))
    )
    (net (code "34") (name "/SW8") (class "Default")
      (node (ref "IC17") (pin "8") (pinfunction "P07_8") (pintype "bidirectional"))
      (node (ref "R125") (pin "1") (pinfunction "1_1") (pintype "passive"))
      (node (ref "T24") (pin "1") (pinfunction "G_1") (pintype "passive"))
    )
    (net (code "35") (name "/SW9") (class "Default")
      (node (ref "IC17") (pin "10") (pinfunction "P10_10") (pintype "bidirectional"))
      (node (ref "R62") (pin "1") (pinfunction "1_1") (pintype "passive"))
      (node (ref "T13") (pin "1") (pinfunction "G_1") (pintype "passive"))
    )
    (net (code "36") (name "/SW10") (class "Default")
      (node (ref "IC17") (pin "11") (pinfunction "P11_11") (pintype "bidirectional"))
      (node (ref "R63") (pin "1") (pinfunction "1_1") (pintype "passive"))
      (node (ref "T14") (pin "1") (pinfunction "G_1") (pintype "passive"))
    )
    (net (code "37") (name "/VCM") (class "Default")
      (node (ref "J31") (pin "33") (pinfunction "33_33") (pintype "bidirectional"))
    )
    (net (code "38") (name "GND") (class "Default")
      (node (ref "C39") (pin "2") (pinfunction "2_2") (pintype "passive"))
      (node (ref "C40") (pin "1") (pinfunction "1_1") (pintype "passive"))
      (node (ref "C42") (pin "1") (pinfunction "1_1") (pintype "passive"))
      (node (ref "IC14") (pin "2") (pinfunction "VSS_2") (pintype "power_in"))
      (node (ref "IC15") (pin "18") (pinfunction "A0_18") (pintype "bidirectional"))
      (node (ref "IC15") (pin "23") (pinfunction "A1_23") (pintype "bidirectional"))
      (node (ref "IC15") (pin "9") (pinfunction "GND_9") (pintype "power_in"))
      (node (ref "IC16") (pin "4") (pinfunction "GND_4") (pintype "power_in"))
      (node (ref "IC16") (pin "5") (pinfunction "A2_5") (pintype "input"))
      (node (ref "IC16") (pin "6") (pinfunction "A1_6") (pintype "input"))
      (node (ref "IC16") (pin "7") (pinfunction "A0_7") (pintype "input"))
      (node (ref "IC17") (pin "23") (pinfunction "A1_23") (pintype "bidirectional"))
      (node (ref "IC17") (pin "9") (pinfunction "GND_9") (pintype "power_in"))
      (node (ref "J1") (pin "2") (pinfunction "2_2") (pintype "bidirectional"))
      (node (ref "J2") (pin "2") (pinfunction "2_2") (pintype "bidirectional"))
      (node (ref "J25") (pin "2") (pinfunction "2_2") (pintype "bidirectional"))
      (node (ref "J26") (pin "2") (pinfunction "2_2") (pintype "bidirectional"))
      (node (ref "J27") (pin "2") (pinfunction "2_2") (pintype "bidirectional"))
      (node (ref "J28") (pin "2") (pinfunction "2_2") (pintype "bidirectional"))
      (node (ref "J29") (pin "2") (pinfunction "2_2") (pintype "bidirectional"))
      (node (ref "J3") (pin "2") (pinfunction "2_2") (pintype "bidirectional"))
      (node (ref "J30") (pin "2") (pinfunction "2_2") (pintype "bidirectional"))
      (node (ref "J31") (pin "1") (pinfunction "1_1") (pintype "bidirectional"))
      (node (ref "J31") (pin "2") (pinfunction "2_2") (pintype "bidirectional"))
      (node (ref "J31") (pin "23") (pinfunction "23_23") (pintype "bidirectional"))
      (node (ref "J31") (pin "24") (pinfunction "24_24") (pintype "bidirectional"))
      (node (ref "J31") (pin "29") (pinfunction "29_29") (pintype "bidirectional"))
      (node (ref "J31") (pin "30") (pinfunction "30_30") (pintype "bidirectional"))
      (node (ref "J31") (pin "35") (pinfunction "35_35") (pintype "bidirectional"))
      (node (ref "J31") (pin "36") (pinfunction "36_36") (pintype "bidirectional"))
      (node (ref "R123") (pin "2") (pinfunction "2_2") (pintype "passive"))
      (node (ref "R124") (pin "2") (pinfunction "2_2") (pintype "passive"))
      (node (ref "R125") (pin "2") (pinfunction "2_2") (pintype "passive"))
      (node (ref "R62") (pin "2") (pinfunction "2_2") (pintype "passive"))
      (node (ref "R63") (pin "2") (pinfunction "2_2") (pintype "passive"))
      (node (ref "R84") (pin "2") (pinfunction "2_2") (pintype "passive"))
      (node (ref "R85") (pin "2") (pinfunction "2_2") (pintype "passive"))
      (node (ref "R86") (pin "2") (pinfunction "2_2") (pintype "passive"))
      (node (ref "R87") (pin "2") (pinfunction "2_2") (pintype "passive"))
      (node (ref "R88") (pin "2") (pinfunction "2_2") (pintype "passive"))
      (node (ref "SW4") (pin "3") (pinfunction "3_3") (pintype "passive"))
      (node (ref "SW4") (pin "4") (pinfunction "4_4") (pintype "passive"))
      (node (ref "SW7") (pin "10") (pinfunction "10_10") (pintype "passive"))
      (node (ref "SW7") (pin "11") (pinfunction "11_11") (pintype "passive"))
      (node (ref "SW7") (pin "12") (pinfunction "12_12") (pintype "passive"))
      (node (ref "SW7") (pin "13") (pinfunction "13_13") (pintype "passive"))
      (node (ref "SW7") (pin "14") (pinfunction "14_14") (pintype "passive"))
      (node (ref "SW7") (pin "15") (pinfunction "15_15") (pintype "passive"))
      (node (ref "SW7") (pin "16") (pinfunction "16_16") (pintype "passive"))
      (node (ref "SW7") (pin "9") (pinfunction "9_9") (pintype "passive"))
      (node (ref "T15") (pin "2") (pinfunction "S_2") (pintype "passive"))
      (node (ref "T16") (pin "2") (pinfunction "S_2") (pintype "passive"))
      (node (ref "T17") (pin "2") (pinfunction "S_2") (pintype "passive"))
      (node (ref "T18") (pin "2") (pinfunction "S_2") (pintype "passive"))
      (node (ref "T19") (pin "2") (pinfunction "S_2") (pintype "passive"))
      (node (ref "T20") (pin "2") (pinfunction "S_2") (pintype "passive"))
      (node (ref "T21") (pin "2") (pinfunction "S_2") (pintype "passive"))
      (node (ref "T22") (pin "2") (pinfunction "S_2") (pintype "passive"))
      (node (ref "T23") (pin "2") (pinfunction "S_2") (pintype "passive"))
      (node (ref "T24") (pin "2") (pinfunction "S_2") (pintype "passive"))
      (node (ref "TR2") (pin "1") (pinfunction "P1_1") (pintype "passive"))
      (node (ref "TR2") (pin "2") (pinfunction "P1_2") (pintype "passive"))
      (node (ref "TR2") (pin "5") (pinfunction "NC_5") (pintype "passive"))
    )
    (net (code "39") (name "N6V0A") (class "Default")
      (node (ref "J31") (pin "31") (pinfunction "31_31") (pintype "bidirectional"))
      (node (ref "R66") (pin "2") (pinfunction "2_2") (pintype "passive"))
      (node (ref "R67") (pin "2") (pinfunction "2_2") (pintype "passive"))
      (node (ref "R78") (pin "1") (pinfunction "1_1") (pintype "passive"))
      (node (ref "R80") (pin "1") (pinfunction "1_1") (pintype "passive"))
      (node (ref "TP9") (pin "1") (pinfunction "1_1") (pintype "bidirectional"))
    )
    (net (code "40") (name "N12V0A") (class "Default")
      (node (ref "J31") (pin "25") (pinfunction "25_25") (pintype "bidirectional"))
      (node (ref "R64") (pin "1") (pinfunction "1_1") (pintype "passive"))
      (node (ref "R68") (pin "1") (pinfunction "1_1") (pintype "passive"))
      (node (ref "TP7") (pin "1") (pinfunction "1_1") (pintype "bidirectional"))
    )
    (net (code "41") (name "Net-(J26-Pad1)") (class "Default")
      (node (ref "J26") (pin "1") (pinfunction "1_1") (pintype "bidirectional"))
      (node (ref "TR2") (pin "3") (pinfunction "P1_3") (pintype "passive"))
    )
    (net (code "42") (name "Net-(R56-Pad2)") (class "Default")
      (node (ref "R56") (pin "2") (pinfunction "2_2") (pintype "passive"))
      (node (ref "R57") (pin "1") (pinfunction "1_1") (pintype "passive"))
    )
    (net (code "43") (name "Net-(R57-Pad2)") (class "Default")
      (node (ref "R57") (pin "2") (pinfunction "2_2") (pintype "passive"))
      (node (ref "R58") (pin "1") (pinfunction "1_1") (pintype "passive"))
    )
    (net (code "44") (name "Net-(R59-Pad2)") (class "Default")
      (node (ref "R59") (pin "2") (pinfunction "2_2") (pintype "passive"))
      (node (ref "R60") (pin "1") (pinfunction "1_1") (pintype "passive"))
    )
    (net (code "45") (name "Net-(R60-Pad2)") (class "Default")
      (node (ref "R60") (pin "2") (pinfunction "2_2") (pintype "passive"))
      (node (ref "R61") (pin "1") (pinfunction "1_1") (pintype "passive"))
    )
    (net (code "46") (name "Net-(R64-Pad2)") (class "Default")
      (node (ref "R64") (pin "2") (pinfunction "2_2") (pintype "passive"))
      (node (ref "R65") (pin "1") (pinfunction "1_1") (pintype "passive"))
    )
    (net (code "47") (name "Net-(R68-Pad2)") (class "Default")
      (node (ref "R68") (pin "2") (pinfunction "2_2") (pintype "passive"))
      (node (ref "R69") (pin "1") (pinfunction "1_1") (pintype "passive"))
    )
    (net (code "48") (name "Net-(R70-Pad2)") (class "Default")
      (node (ref "R70") (pin "2") (pinfunction "2_2") (pintype "passive"))
      (node (ref "R71") (pin "1") (pinfunction "1_1") (pintype "passive"))
    )
    (net (code "49") (name "Net-(R71-Pad2)") (class "Default")
      (node (ref "R71") (pin "2") (pinfunction "2_2") (pintype "passive"))
      (node (ref "R72") (pin "1") (pinfunction "1_1") (pintype "passive"))
    )
    (net (code "50") (name "Net-(R72-Pad2)") (class "Default")
      (node (ref "R72") (pin "2") (pinfunction "2_2") (pintype "passive"))
      (node (ref "R73") (pin "1") (pinfunction "1_1") (pintype "passive"))
    )
    (net (code "51") (name "Net-(R74-Pad2)") (class "Default")
      (node (ref "R74") (pin "2") (pinfunction "2_2") (pintype "passive"))
      (node (ref "R75") (pin "1") (pinfunction "1_1") (pintype "passive"))
    )
    (net (code "52") (name "Net-(R75-Pad2)") (class "Default")
      (node (ref "R75") (pin "2") (pinfunction "2_2") (pintype "passive"))
      (node (ref "R76") (pin "1") (pinfunction "1_1") (pintype "passive"))
    )
    (net (code "53") (name "Net-(R76-Pad2)") (class "Default")
      (node (ref "R76") (pin "2") (pinfunction "2_2") (pintype "passive"))
      (node (ref "R77") (pin "1") (pinfunction "1_1") (pintype "passive"))
    )
    (net (code "54") (name "Net-(R78-Pad2)") (class "Default")
      (node (ref "R78") (pin "2") (pinfunction "2_2") (pintype "passive"))
      (node (ref "R79") (pin "1") (pinfunction "1_1") (pintype "passive"))
    )
    (net (code "55") (name "Net-(R80-Pad2)") (class "Default")
      (node (ref "R80") (pin "2") (pinfunction "2_2") (pintype "passive"))
      (node (ref "R81") (pin "1") (pinfunction "1_1") (pintype "passive"))
    )
    (net (code "56") (name "Net-(R82-Pad2)") (class "Default")
      (node (ref "R82") (pin "2") (pinfunction "2_2") (pintype "passive"))
      (node (ref "R83") (pin "1") (pinfunction "1_1") (pintype "passive"))
    )
    (net (code "57") (name "Net-(R126-Pad2)") (class "Default")
      (node (ref "R126") (pin "2") (pinfunction "2_2") (pintype "passive"))
      (node (ref "R127") (pin "1") (pinfunction "1_1") (pintype "passive"))
    )
    (net (code "58") (name "Net-(T13-D)") (class "Default")
      (node (ref "R66") (pin "1") (pinfunction "1_1") (pintype "passive"))
      (node (ref "T13") (pin "3") (pinfunction "D_3") (pintype "passive"))
      (node (ref "T15") (pin "1") (pinfunction "G_1") (pintype "passive"))
    )
    (net (code "59") (name "Net-(T14-D)") (class "Default")
      (node (ref "R67") (pin "1") (pinfunction "1_1") (pintype "passive"))
      (node (ref "T14") (pin "3") (pinfunction "D_3") (pintype "passive"))
      (node (ref "T16") (pin "1") (pinfunction "G_1") (pintype "passive"))
    )
    (net (code "60") (name "Net-(T15-D)") (class "Default")
      (node (ref "R79") (pin "2") (pinfunction "2_2") (pintype "passive"))
      (node (ref "SW7") (pin "5") (pinfunction "5_5") (pintype "passive"))
      (node (ref "T15") (pin "3") (pinfunction "D_3") (pintype "passive"))
    )
    (net (code "61") (name "Net-(T16-D)") (class "Default")
      (node (ref "R81") (pin "2") (pinfunction "2_2") (pintype "passive"))
      (node (ref "SW7") (pin "6") (pinfunction "6_6") (pintype "passive"))
      (node (ref "T16") (pin "3") (pinfunction "D_3") (pintype "passive"))
    )
    (net (code "62") (name "Net-(T17-D)") (class "Default")
      (node (ref "R127") (pin "2") (pinfunction "2_2") (pintype "passive"))
      (node (ref "SW7") (pin "8") (pinfunction "8_8") (pintype "passive"))
      (node (ref "T17") (pin "3") (pinfunction "D_3") (pintype "passive"))
    )
    (net (code "63") (name "Net-(T18-D)") (class "Default")
      (node (ref "R83") (pin "2") (pinfunction "2_2") (pintype "passive"))
      (node (ref "SW7") (pin "7") (pinfunction "7_7") (pintype "passive"))
      (node (ref "T18") (pin "3") (pinfunction "D_3") (pintype "passive"))
    )
    (net (code "64") (name "Net-(T19-D)") (class "Default")
      (node (ref "R77") (pin "2") (pinfunction "2_2") (pintype "passive"))
      (node (ref "SW7") (pin "4") (pinfunction "4_4") (pintype "passive"))
      (node (ref "T19") (pin "3") (pinfunction "D_3") (pintype "passive"))
    )
    (net (code "65") (name "Net-(T20-D)") (class "Default")
      (node (ref "R73") (pin "2") (pinfunction "2_2") (pintype "passive"))
      (node (ref "SW7") (pin "3") (pinfunction "3_3") (pintype "passive"))
      (node (ref "T20") (pin "3") (pinfunction "D_3") (pintype "passive"))
    )
    (net (code "66") (name "Net-(T21-D)") (class "Default")
      (node (ref "R69") (pin "2") (pinfunction "2_2") (pintype "passive"))
      (node (ref "SW7") (pin "2") (pinfunction "2_2") (pintype "passive"))
      (node (ref "T21") (pin "3") (pinfunction "D_3") (pintype "passive"))
    )
    (net (code "67") (name "Net-(T22-D)") (class "Default")
      (node (ref "R65") (pin "2") (pinfunction "2_2") (pintype "passive"))
      (node (ref "SW7") (pin "1") (pinfunction "1_1") (pintype "passive"))
      (node (ref "T22") (pin "3") (pinfunction "D_3") (pintype "passive"))
    )
    (net (code "68") (name "Net-(T23-D)") (class "Default")
      (node (ref "R61") (pin "2") (pinfunction "2_2") (pintype "passive"))
      (node (ref "SW4") (pin "2") (pinfunction "2_2") (pintype "passive"))
      (node (ref "T23") (pin "3") (pinfunction "D_3") (pintype "passive"))
    )
    (net (code "69") (name "Net-(T24-D)") (class "Default")
      (node (ref "R58") (pin "2") (pinfunction "2_2") (pintype "passive"))
      (node (ref "SW4") (pin "1") (pinfunction "1_1") (pintype "passive"))
      (node (ref "T24") (pin "3") (pinfunction "D_3") (pintype "passive"))
    )
    (net (code "70") (name "P3V3") (class "Default")
      (node (ref "C42") (pin "2") (pinfunction "2_2") (pintype "passive"))
      (node (ref "IC14") (pin "4") (pinfunction "VCC_4") (pintype "power_in"))
      (node (ref "IC15") (pin "21") (pinfunction "VCC_21") (pintype "power_in"))
      (node (ref "IC15") (pin "24") (pinfunction "~{RESET}_24") (pintype "input"))
      (node (ref "IC16") (pin "8") (pinfunction "+VS_8") (pintype "power_in"))
      (node (ref "IC17") (pin "18") (pinfunction "A0_18") (pintype "bidirectional"))
      (node (ref "IC17") (pin "21") (pinfunction "VCC_21") (pintype "power_in"))
      (node (ref "IC17") (pin "24") (pinfunction "~{RESET}_24") (pintype "input"))
      (node (ref "J31") (pin "19") (pinfunction "19_19") (pintype "bidirectional"))
      (node (ref "R126") (pin "1") (pinfunction "1_1") (pintype "passive"))
      (node (ref "R82") (pin "1") (pinfunction "1_1") (pintype "passive"))
      (node (ref "T13") (pin "2") (pinfunction "S_2") (pintype "passive"))
      (node (ref "T14") (pin "2") (pinfunction "S_2") (pintype "passive"))
      (node (ref "TP10") (pin "1") (pinfunction "1_1") (pintype "bidirectional"))
    )
    (net (code "71") (name "P6V0A") (class "Default")
      (node (ref "J31") (pin "32") (pinfunction "32_32") (pintype "bidirectional"))
      (node (ref "J31") (pin "34") (pinfunction "34_34") (pintype "bidirectional"))
      (node (ref "R70") (pin "1") (pinfunction "1_1") (pintype "passive"))
      (node (ref "R74") (pin "1") (pinfunction "1_1") (pintype "passive"))
      (node (ref "TP8") (pin "1") (pinfunction "1_1") (pintype "bidirectional"))
    )
    (net (code "72") (name "P12V0A") (class "Default")
      (node (ref "J31") (pin "26") (pinfunction "26_26") (pintype "bidirectional"))
      (node (ref "R56") (pin "1") (pinfunction "1_1") (pintype "passive"))
      (node (ref "R59") (pin "1") (pinfunction "1_1") (pintype "passive"))
      (node (ref "TP6") (pin "1") (pinfunction "1_1") (pintype "bidirectional"))
    )
    (net (code "73") (name "unconnected-(IC14-NC-Pad5)") (class "Default")
      (node (ref "IC14") (pin "5") (pinfunction "NC_5") (pintype "passive"))
    )
    (net (code "74") (name "unconnected-(IC15-~{INT}-Pad22)") (class "Default")
      (node (ref "IC15") (pin "22") (pinfunction "~{INT}_22") (pintype "output"))
    )
    (net (code "75") (name "unconnected-(IC16-O.S.-Pad3)") (class "Default")
      (node (ref "IC16") (pin "3") (pinfunction "O.S._3") (pintype "output"))
    )
    (net (code "76") (name "unconnected-(IC17-P12-Pad12)") (class "Default")
      (node (ref "IC17") (pin "12") (pinfunction "P12_12") (pintype "bidirectional"))
    )
    (net (code "77") (name "unconnected-(IC17-P13-Pad13)") (class "Default")
      (node (ref "IC17") (pin "13") (pinfunction "P13_13") (pintype "bidirectional"))
    )
    (net (code "78") (name "unconnected-(IC17-P14-Pad14)") (class "Default")
      (node (ref "IC17") (pin "14") (pinfunction "P14_14") (pintype "bidirectional"))
    )
    (net (code "79") (name "unconnected-(IC17-P15-Pad15)") (class "Default")
      (node (ref "IC17") (pin "15") (pinfunction "P15_15") (pintype "bidirectional"))
    )
    (net (code "80") (name "unconnected-(IC17-P16-Pad16)") (class "Default")
      (node (ref "IC17") (pin "16") (pinfunction "P16_16") (pintype "bidirectional"))
    )
    (net (code "81") (name "unconnected-(IC17-P17-Pad17)") (class "Default")
      (node (ref "IC17") (pin "17") (pinfunction "P17_17") (pintype "bidirectional"))
    )
    (net (code "82") (name "unconnected-(IC17-~{INT}-Pad22)") (class "Default")
      (node (ref "IC17") (pin "22") (pinfunction "~{INT}_22") (pintype "output"))
    )
    (net (code "83") (name "unconnected-(J31-Pad20)") (class "Default")
      (node (ref "J31") (pin "20") (pinfunction "20_20") (pintype "bidirectional"))
    )
    (net (code "84") (name "unconnected-(J31-Pad27)") (class "Default")
      (node (ref "J31") (pin "27") (pinfunction "27_27") (pintype "bidirectional"))
    )
    (net (code "85") (name "unconnected-(J31-Pad28)") (class "Default")
      (node (ref "J31") (pin "28") (pinfunction "28_28") (pintype "bidirectional"))
    )
    (net (code "86") (name "unconnected-(J31-Pad37)") (class "Default")
      (node (ref "J31") (pin "37") (pinfunction "37_37") (pintype "bidirectional"))
    )
    (net (code "87") (name "unconnected-(J31-Pad38)") (class "Default")
      (node (ref "J31") (pin "38") (pinfunction "38_38") (pintype "bidirectional"))
    )
    (net (code "88") (name "unconnected-(J31-Pad39)") (class "Default")
      (node (ref "J31") (pin "39") (pinfunction "39_39") (pintype "bidirectional"))
    )
    (net (code "89") (name "unconnected-(J31-Pad40)") (class "Default")
      (node (ref "J31") (pin "40") (pinfunction "40_40") (pintype "bidirectional"))
    )
  )
)
